# adapter.net
KiCad netlist of a schematic drawn in EAGLE
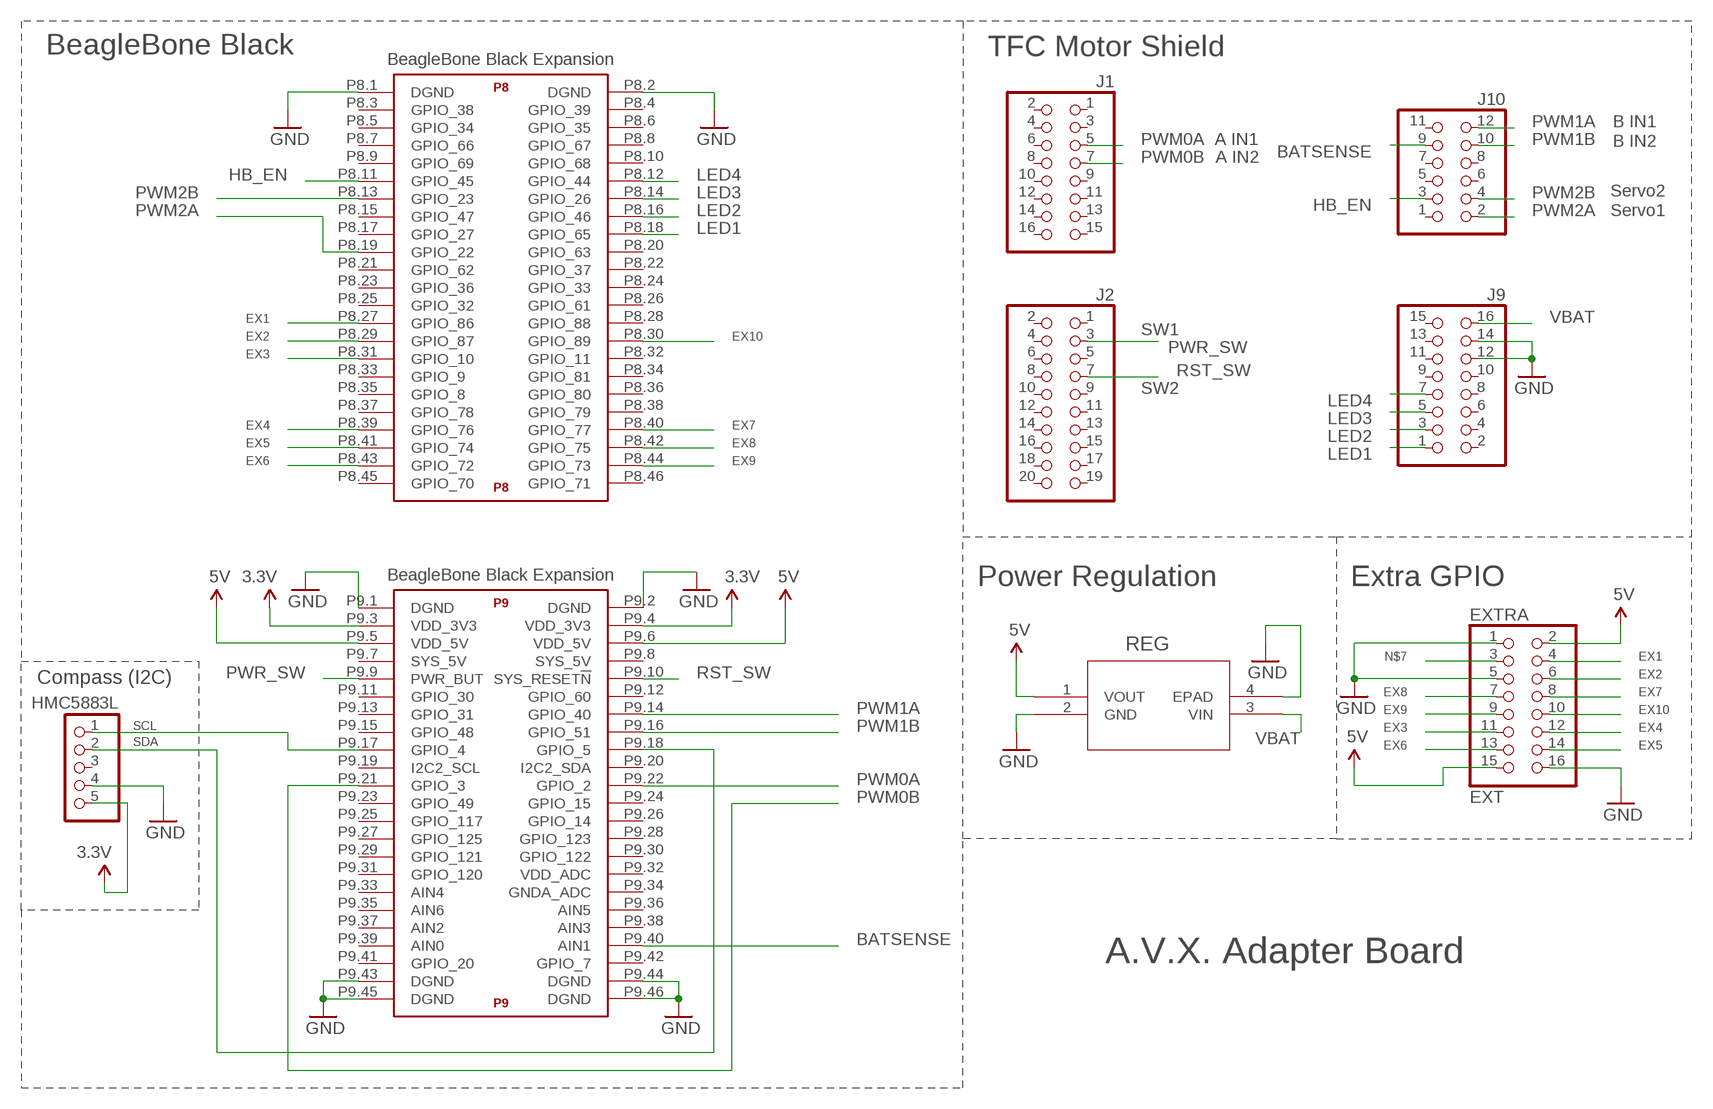
[diagram p0: schematic, sheet 1]

(export (version "E")
  (design (tool "Eeschema 10.0.6"))
  (components
    (comp (ref "COMPASS")
      (value "HMC5883L")
      (footprint "eagle-import:1X05")
      (libsource (lib "eagle-import") (part "PINHD-1X5"))
    )
    (comp (ref "EXTRA")
      (value "EXT")
      (footprint "eagle-import:2X08")
      (libsource (lib "eagle-import") (part "PINHD-2X8"))
    )
    (comp (ref "J1")
      (value "PINHD-2X8")
      (footprint "eagle-import:2X08")
      (libsource (lib "eagle-import") (part "PINHD-2X8"))
    )
    (comp (ref "J2")
      (value "PINHD-2X10")
      (footprint "eagle-import:2X10")
      (libsource (lib "eagle-import") (part "PINHD-2X10"))
    )
    (comp (ref "J9")
      (value "PINHD-2X8")
      (footprint "eagle-import:2X08")
      (libsource (lib "eagle-import") (part "PINHD-2X8"))
    )
    (comp (ref "J10")
      (value "PINHD-2X6")
      (footprint "eagle-import:2X06")
      (libsource (lib "eagle-import") (part "PINHD-2X6"))
    )
    (comp (ref "REG")
      (value "UCC383-5_KTT_3")
      (footprint "eagle-import:KTT3_6P22X6P6")
      (fields
        (field (name "GENERIC_PART_NUMBER") "UCC383-5")
        (field (name "MANUFACTURER") "Texas Instruments")
        (field (name "MANUFACTURER_PART_NUMBER") "ucc383-5_ktt_3")
      )
      (libsource (lib "eagle-import") (part "UCC383-5_KTT_3"))
    )
    (comp (ref "U$1")
      (value "BEAGLE_BONE_BLACK_CAPE")
      (footprint "eagle-import:BEAGLE_BONE_BLACK_CAPE")
      (libsource (lib "eagle-import") (part "BEAGLE_BONE_BLACK_CAPE"))
    )
  )
  (nets
    (net (code "1") (name "/BATSENSE") (class "Default")
      (node (ref "J10") (pin "9") (pinfunction "9_9") (pintype "passive"))
      (node (ref "U$1") (pin "P9.40") (pinfunction "AIN1_P9.40") (pintype "bidirectional"))
    )
    (net (code "2") (name "/EX1") (class "Default")
      (node (ref "EXTRA") (pin "4") (pinfunction "4_4") (pintype "passive"))
      (node (ref "U$1") (pin "P8.27") (pinfunction "GPIO_86_P8.27") (pintype "bidirectional"))
    )
    (net (code "3") (name "/EX2") (class "Default")
      (node (ref "EXTRA") (pin "6") (pinfunction "6_6") (pintype "passive"))
      (node (ref "U$1") (pin "P8.29") (pinfunction "GPIO_87_P8.29") (pintype "bidirectional"))
    )
    (net (code "4") (name "/EX3") (class "Default")
      (node (ref "EXTRA") (pin "11") (pinfunction "11_11") (pintype "passive"))
      (node (ref "U$1") (pin "P8.31") (pinfunction "GPIO_10_P8.31") (pintype "bidirectional"))
    )
    (net (code "5") (name "/EX4") (class "Default")
      (node (ref "EXTRA") (pin "12") (pinfunction "12_12") (pintype "passive"))
      (node (ref "U$1") (pin "P8.39") (pinfunction "GPIO_76_P8.39") (pintype "bidirectional"))
    )
    (net (code "6") (name "/EX5") (class "Default")
      (node (ref "EXTRA") (pin "14") (pinfunction "14_14") (pintype "passive"))
      (node (ref "U$1") (pin "P8.41") (pinfunction "GPIO_74_P8.41") (pintype "bidirectional"))
    )
    (net (code "7") (name "/EX6") (class "Default")
      (node (ref "EXTRA") (pin "13") (pinfunction "13_13") (pintype "passive"))
      (node (ref "U$1") (pin "P8.43") (pinfunction "GPIO_72_P8.43") (pintype "bidirectional"))
    )
    (net (code "8") (name "/EX7") (class "Default")
      (node (ref "EXTRA") (pin "8") (pinfunction "8_8") (pintype "passive"))
      (node (ref "U$1") (pin "P8.40") (pinfunction "GPIO_77_P8.40") (pintype "bidirectional"))
    )
    (net (code "9") (name "/EX8") (class "Default")
      (node (ref "EXTRA") (pin "7") (pinfunction "7_7") (pintype "passive"))
      (node (ref "U$1") (pin "P8.42") (pinfunction "GPIO_75_P8.42") (pintype "bidirectional"))
    )
    (net (code "10") (name "/EX9") (class "Default")
      (node (ref "EXTRA") (pin "9") (pinfunction "9_9") (pintype "passive"))
      (node (ref "U$1") (pin "P8.44") (pinfunction "GPIO_73_P8.44") (pintype "bidirectional"))
    )
    (net (code "11") (name "/EX10") (class "Default")
      (node (ref "EXTRA") (pin "10") (pinfunction "10_10") (pintype "passive"))
      (node (ref "U$1") (pin "P8.30") (pinfunction "GPIO_89_P8.30") (pintype "bidirectional"))
    )
    (net (code "12") (name "/HB_EN") (class "Default")
      (node (ref "J10") (pin "3") (pinfunction "3_3") (pintype "passive"))
      (node (ref "U$1") (pin "P8.11") (pinfunction "GPIO_45_P8.11") (pintype "bidirectional"))
    )
    (net (code "13") (name "/LED1") (class "Default")
      (node (ref "J9") (pin "1") (pinfunction "1_1") (pintype "passive"))
      (node (ref "U$1") (pin "P8.18") (pinfunction "GPIO_65_P8.18") (pintype "bidirectional"))
    )
    (net (code "14") (name "/LED2") (class "Default")
      (node (ref "J9") (pin "3") (pinfunction "3_3") (pintype "passive"))
      (node (ref "U$1") (pin "P8.16") (pinfunction "GPIO_46_P8.16") (pintype "bidirectional"))
    )
    (net (code "15") (name "/LED3") (class "Default")
      (node (ref "J9") (pin "5") (pinfunction "5_5") (pintype "passive"))
      (node (ref "U$1") (pin "P8.14") (pinfunction "GPIO_26_P8.14") (pintype "bidirectional"))
    )
    (net (code "16") (name "/LED4") (class "Default")
      (node (ref "J9") (pin "7") (pinfunction "7_7") (pintype "passive"))
      (node (ref "U$1") (pin "P8.12") (pinfunction "GPIO_44_P8.12") (pintype "bidirectional"))
    )
    (net (code "17") (name "/N$7") (class "Default")
      (node (ref "EXTRA") (pin "3") (pinfunction "3_3") (pintype "passive"))
    )
    (net (code "18") (name "/PWM0A") (class "Default")
      (node (ref "J1") (pin "5") (pinfunction "5_5") (pintype "passive"))
      (node (ref "U$1") (pin "P9.22") (pinfunction "GPIO_2_P9.22") (pintype "bidirectional"))
    )
    (net (code "19") (name "/PWM0B") (class "Default")
      (node (ref "J1") (pin "7") (pinfunction "7_7") (pintype "passive"))
      (node (ref "U$1") (pin "P9.21") (pinfunction "GPIO_3_P9.21") (pintype "bidirectional"))
    )
    (net (code "20") (name "/PWM1A") (class "Default")
      (node (ref "J10") (pin "12") (pinfunction "12_12") (pintype "passive"))
      (node (ref "U$1") (pin "P9.14") (pinfunction "GPIO_40_P9.14") (pintype "bidirectional"))
    )
    (net (code "21") (name "/PWM1B") (class "Default")
      (node (ref "J10") (pin "10") (pinfunction "10_10") (pintype "passive"))
      (node (ref "U$1") (pin "P9.16") (pinfunction "GPIO_51_P9.16") (pintype "bidirectional"))
    )
    (net (code "22") (name "/PWM2A") (class "Default")
      (node (ref "J10") (pin "2") (pinfunction "2_2") (pintype "passive"))
      (node (ref "U$1") (pin "P8.19") (pinfunction "GPIO_22_P8.19") (pintype "bidirectional"))
    )
    (net (code "23") (name "/PWM2B") (class "Default")
      (node (ref "J10") (pin "4") (pinfunction "4_4") (pintype "passive"))
      (node (ref "U$1") (pin "P8.13") (pinfunction "GPIO_23_P8.13") (pintype "bidirectional"))
    )
    (net (code "24") (name "/PWR_SW") (class "Default")
      (node (ref "J2") (pin "3") (pinfunction "3_3") (pintype "passive"))
      (node (ref "U$1") (pin "P9.9") (pinfunction "PWR_BUT_P9.9") (pintype "bidirectional"))
    )
    (net (code "25") (name "/RST_SW") (class "Default")
      (node (ref "J2") (pin "7") (pinfunction "7_7") (pintype "passive"))
      (node (ref "U$1") (pin "P9.10") (pinfunction "SYS_RESET~{N}_P9.10") (pintype "bidirectional"))
    )
    (net (code "26") (name "/VBAT") (class "Default")
      (node (ref "J9") (pin "16") (pinfunction "16_16") (pintype "passive"))
      (node (ref "REG") (pin "3") (pinfunction "VIN_3") (pintype "input"))
    )
    (net (code "27") (name "3.3V") (class "Default")
      (node (ref "COMPASS") (pin "5") (pinfunction "5_5") (pintype "passive"))
      (node (ref "U$1") (pin "P9.3") (pinfunction "VDD_3V3_P9.3") (pintype "bidirectional"))
      (node (ref "U$1") (pin "P9.4") (pinfunction "VDD_3V3_P9.4") (pintype "bidirectional"))
    )
    (net (code "28") (name "5V") (class "Default")
      (node (ref "EXTRA") (pin "15") (pinfunction "15_15") (pintype "passive"))
      (node (ref "EXTRA") (pin "2") (pinfunction "2_2") (pintype "passive"))
      (node (ref "REG") (pin "1") (pinfunction "VOUT_1") (pintype "output"))
      (node (ref "U$1") (pin "P9.5") (pinfunction "VDD_5V_P9.5") (pintype "bidirectional"))
      (node (ref "U$1") (pin "P9.6") (pinfunction "VDD_5V_P9.6") (pintype "bidirectional"))
    )
    (net (code "29") (name "GND") (class "Default")
      (node (ref "COMPASS") (pin "4") (pinfunction "4_4") (pintype "passive"))
      (node (ref "EXTRA") (pin "1") (pinfunction "1_1") (pintype "passive"))
      (node (ref "EXTRA") (pin "16") (pinfunction "16_16") (pintype "passive"))
      (node (ref "EXTRA") (pin "5") (pinfunction "5_5") (pintype "passive"))
      (node (ref "J9") (pin "12") (pinfunction "12_12") (pintype "passive"))
      (node (ref "J9") (pin "14") (pinfunction "14_14") (pintype "passive"))
      (node (ref "REG") (pin "2") (pinfunction "GND_2") (pintype "power_in"))
      (node (ref "REG") (pin "4") (pinfunction "EPAD_4") (pintype "passive"))
      (node (ref "U$1") (pin "P8.1") (pinfunction "DGND_P8.1") (pintype "bidirectional"))
      (node (ref "U$1") (pin "P8.2") (pinfunction "DGND_P8.2") (pintype "bidirectional"))
      (node (ref "U$1") (pin "P9.1") (pinfunction "DGND_P9.1") (pintype "bidirectional"))
      (node (ref "U$1") (pin "P9.2") (pinfunction "DGND_P9.2") (pintype "bidirectional"))
      (node (ref "U$1") (pin "P9.43") (pinfunction "DGND_P9.43") (pintype "bidirectional"))
      (node (ref "U$1") (pin "P9.44") (pinfunction "DGND_P9.44") (pintype "bidirectional"))
      (node (ref "U$1") (pin "P9.45") (pinfunction "DGND_P9.45") (pintype "bidirectional"))
      (node (ref "U$1") (pin "P9.46") (pinfunction "DGND_P9.46") (pintype "bidirectional"))
    )
    (net (code "30") (name "Net-(U$1B-GPIO_4)") (class "Default")
      (node (ref "COMPASS") (pin "1") (pinfunction "1_1") (pintype "passive"))
      (node (ref "U$1") (pin "P9.17") (pinfunction "GPIO_4_P9.17") (pintype "bidirectional"))
    )
    (net (code "31") (name "Net-(U$1B-GPIO_5)") (class "Default")
      (node (ref "COMPASS") (pin "2") (pinfunction "2_2") (pintype "passive"))
      (node (ref "U$1") (pin "P9.18") (pinfunction "GPIO_5_P9.18") (pintype "bidirectional"))
    )
    (net (code "32") (name "unconnected-(COMPASS-Pad3)") (class "Default")
      (node (ref "COMPASS") (pin "3") (pinfunction "3_3") (pintype "passive"))
    )
    (net (code "33") (name "unconnected-(J1-Pad1)") (class "Default")
      (node (ref "J1") (pin "1") (pinfunction "1_1") (pintype "passive"))
    )
    (net (code "34") (name "unconnected-(J1-Pad2)") (class "Default")
      (node (ref "J1") (pin "2") (pinfunction "2_2") (pintype "passive"))
    )
    (net (code "35") (name "unconnected-(J1-Pad3)") (class "Default")
      (node (ref "J1") (pin "3") (pinfunction "3_3") (pintype "passive"))
    )
    (net (code "36") (name "unconnected-(J1-Pad4)") (class "Default")
      (node (ref "J1") (pin "4") (pinfunction "4_4") (pintype "passive"))
    )
    (net (code "37") (name "unconnected-(J1-Pad6)") (class "Default")
      (node (ref "J1") (pin "6") (pinfunction "6_6") (pintype "passive"))
    )
    (net (code "38") (name "unconnected-(J1-Pad8)") (class "Default")
      (node (ref "J1") (pin "8") (pinfunction "8_8") (pintype "passive"))
    )
    (net (code "39") (name "unconnected-(J1-Pad9)") (class "Default")
      (node (ref "J1") (pin "9") (pinfunction "9_9") (pintype "passive"))
    )
    (net (code "40") (name "unconnected-(J1-Pad10)") (class "Default")
      (node (ref "J1") (pin "10") (pinfunction "10_10") (pintype "passive"))
    )
    (net (code "41") (name "unconnected-(J1-Pad11)") (class "Default")
      (node (ref "J1") (pin "11") (pinfunction "11_11") (pintype "passive"))
    )
    (net (code "42") (name "unconnected-(J1-Pad12)") (class "Default")
      (node (ref "J1") (pin "12") (pinfunction "12_12") (pintype "passive"))
    )
    (net (code "43") (name "unconnected-(J1-Pad13)") (class "Default")
      (node (ref "J1") (pin "13") (pinfunction "13_13") (pintype "passive"))
    )
    (net (code "44") (name "unconnected-(J1-Pad14)") (class "Default")
      (node (ref "J1") (pin "14") (pinfunction "14_14") (pintype "passive"))
    )
    (net (code "45") (name "unconnected-(J1-Pad15)") (class "Default")
      (node (ref "J1") (pin "15") (pinfunction "15_15") (pintype "passive"))
    )
    (net (code "46") (name "unconnected-(J1-Pad16)") (class "Default")
      (node (ref "J1") (pin "16") (pinfunction "16_16") (pintype "passive"))
    )
    (net (code "47") (name "unconnected-(J2-Pad1)") (class "Default")
      (node (ref "J2") (pin "1") (pinfunction "1_1") (pintype "passive"))
    )
    (net (code "48") (name "unconnected-(J2-Pad2)") (class "Default")
      (node (ref "J2") (pin "2") (pinfunction "2_2") (pintype "passive"))
    )
    (net (code "49") (name "unconnected-(J2-Pad4)") (class "Default")
      (node (ref "J2") (pin "4") (pinfunction "4_4") (pintype "passive"))
    )
    (net (code "50") (name "unconnected-(J2-Pad5)") (class "Default")
      (node (ref "J2") (pin "5") (pinfunction "5_5") (pintype "passive"))
    )
    (net (code "51") (name "unconnected-(J2-Pad6)") (class "Default")
      (node (ref "J2") (pin "6") (pinfunction "6_6") (pintype "passive"))
    )
    (net (code "52") (name "unconnected-(J2-Pad8)") (class "Default")
      (node (ref "J2") (pin "8") (pinfunction "8_8") (pintype "passive"))
    )
    (net (code "53") (name "unconnected-(J2-Pad9)") (class "Default")
      (node (ref "J2") (pin "9") (pinfunction "9_9") (pintype "passive"))
    )
    (net (code "54") (name "unconnected-(J2-Pad10)") (class "Default")
      (node (ref "J2") (pin "10") (pinfunction "10_10") (pintype "passive"))
    )
    (net (code "55") (name "unconnected-(J2-Pad11)") (class "Default")
      (node (ref "J2") (pin "11") (pinfunction "11_11") (pintype "passive"))
    )
    (net (code "56") (name "unconnected-(J2-Pad12)") (class "Default")
      (node (ref "J2") (pin "12") (pinfunction "12_12") (pintype "passive"))
    )
    (net (code "57") (name "unconnected-(J2-Pad13)") (class "Default")
      (node (ref "J2") (pin "13") (pinfunction "13_13") (pintype "passive"))
    )
    (net (code "58") (name "unconnected-(J2-Pad14)") (class "Default")
      (node (ref "J2") (pin "14") (pinfunction "14_14") (pintype "passive"))
    )
    (net (code "59") (name "unconnected-(J2-Pad15)") (class "Default")
      (node (ref "J2") (pin "15") (pinfunction "15_15") (pintype "passive"))
    )
    (net (code "60") (name "unconnected-(J2-Pad16)") (class "Default")
      (node (ref "J2") (pin "16") (pinfunction "16_16") (pintype "passive"))
    )
    (net (code "61") (name "unconnected-(J2-Pad17)") (class "Default")
      (node (ref "J2") (pin "17") (pinfunction "17_17") (pintype "passive"))
    )
    (net (code "62") (name "unconnected-(J2-Pad18)") (class "Default")
      (node (ref "J2") (pin "18") (pinfunction "18_18") (pintype "passive"))
    )
    (net (code "63") (name "unconnected-(J2-Pad19)") (class "Default")
      (node (ref "J2") (pin "19") (pinfunction "19_19") (pintype "passive"))
    )
    (net (code "64") (name "unconnected-(J2-Pad20)") (class "Default")
      (node (ref "J2") (pin "20") (pinfunction "20_20") (pintype "passive"))
    )
    (net (code "65") (name "unconnected-(J9-Pad2)") (class "Default")
      (node (ref "J9") (pin "2") (pinfunction "2_2") (pintype "passive"))
    )
    (net (code "66") (name "unconnected-(J9-Pad4)") (class "Default")
      (node (ref "J9") (pin "4") (pinfunction "4_4") (pintype "passive"))
    )
    (net (code "67") (name "unconnected-(J9-Pad6)") (class "Default")
      (node (ref "J9") (pin "6") (pinfunction "6_6") (pintype "passive"))
    )
    (net (code "68") (name "unconnected-(J9-Pad8)") (class "Default")
      (node (ref "J9") (pin "8") (pinfunction "8_8") (pintype "passive"))
    )
    (net (code "69") (name "unconnected-(J9-Pad9)") (class "Default")
      (node (ref "J9") (pin "9") (pinfunction "9_9") (pintype "passive"))
    )
    (net (code "70") (name "unconnected-(J9-Pad10)") (class "Default")
      (node (ref "J9") (pin "10") (pinfunction "10_10") (pintype "passive"))
    )
    (net (code "71") (name "unconnected-(J9-Pad11)") (class "Default")
      (node (ref "J9") (pin "11") (pinfunction "11_11") (pintype "passive"))
    )
    (net (code "72") (name "unconnected-(J9-Pad13)") (class "Default")
      (node (ref "J9") (pin "13") (pinfunction "13_13") (pintype "passive"))
    )
    (net (code "73") (name "unconnected-(J9-Pad15)") (class "Default")
      (node (ref "J9") (pin "15") (pinfunction "15_15") (pintype "passive"))
    )
    (net (code "74") (name "unconnected-(J10-Pad1)") (class "Default")
      (node (ref "J10") (pin "1") (pinfunction "1_1") (pintype "passive"))
    )
    (net (code "75") (name "unconnected-(J10-Pad5)") (class "Default")
      (node (ref "J10") (pin "5") (pinfunction "5_5") (pintype "passive"))
    )
    (net (code "76") (name "unconnected-(J10-Pad6)") (class "Default")
      (node (ref "J10") (pin "6") (pinfunction "6_6") (pintype "passive"))
    )
    (net (code "77") (name "unconnected-(J10-Pad7)") (class "Default")
      (node (ref "J10") (pin "7") (pinfunction "7_7") (pintype "passive"))
    )
    (net (code "78") (name "unconnected-(J10-Pad8)") (class "Default")
      (node (ref "J10") (pin "8") (pinfunction "8_8") (pintype "passive"))
    )
    (net (code "79") (name "unconnected-(J10-Pad11)") (class "Default")
      (node (ref "J10") (pin "11") (pinfunction "11_11") (pintype "passive"))
    )
    (net (code "80") (name "unconnected-(U$1A-GPIO_8-PadP8.35)") (class "Default")
      (node (ref "U$1") (pin "P8.35") (pinfunction "GPIO_8_P8.35") (pintype "bidirectional"))
    )
    (net (code "81") (name "unconnected-(U$1A-GPIO_9-PadP8.33)") (class "Default")
      (node (ref "U$1") (pin "P8.33") (pinfunction "GPIO_9_P8.33") (pintype "bidirectional"))
    )
    (net (code "82") (name "unconnected-(U$1A-GPIO_11-PadP8.32)") (class "Default")
      (node (ref "U$1") (pin "P8.32") (pinfunction "GPIO_11_P8.32") (pintype "bidirectional"))
    )
    (net (code "83") (name "unconnected-(U$1A-GPIO_27-PadP8.17)") (class "Default")
      (node (ref "U$1") (pin "P8.17") (pinfunction "GPIO_27_P8.17") (pintype "bidirectional"))
    )
    (net (code "84") (name "unconnected-(U$1A-GPIO_32-PadP8.25)") (class "Default")
      (node (ref "U$1") (pin "P8.25") (pinfunction "GPIO_32_P8.25") (pintype "bidirectional"))
    )
    (net (code "85") (name "unconnected-(U$1A-GPIO_33-PadP8.24)") (class "Default")
      (node (ref "U$1") (pin "P8.24") (pinfunction "GPIO_33_P8.24") (pintype "bidirectional"))
    )
    (net (code "86") (name "unconnected-(U$1A-GPIO_34-PadP8.5)") (class "Default")
      (node (ref "U$1") (pin "P8.5") (pinfunction "GPIO_34_P8.5") (pintype "bidirectional"))
    )
    (net (code "87") (name "unconnected-(U$1A-GPIO_35-PadP8.6)") (class "Default")
      (node (ref "U$1") (pin "P8.6") (pinfunction "GPIO_35_P8.6") (pintype "bidirectional"))
    )
    (net (code "88") (name "unconnected-(U$1A-GPIO_36-PadP8.23)") (class "Default")
      (node (ref "U$1") (pin "P8.23") (pinfunction "GPIO_36_P8.23") (pintype "bidirectional"))
    )
    (net (code "89") (name "unconnected-(U$1A-GPIO_37-PadP8.22)") (class "Default")
      (node (ref "U$1") (pin "P8.22") (pinfunction "GPIO_37_P8.22") (pintype "bidirectional"))
    )
    (net (code "90") (name "unconnected-(U$1A-GPIO_38-PadP8.3)") (class "Default")
      (node (ref "U$1") (pin "P8.3") (pinfunction "GPIO_38_P8.3") (pintype "bidirectional"))
    )
    (net (code "91") (name "unconnected-(U$1A-GPIO_39-PadP8.4)") (class "Default")
      (node (ref "U$1") (pin "P8.4") (pinfunction "GPIO_39_P8.4") (pintype "bidirectional"))
    )
    (net (code "92") (name "unconnected-(U$1A-GPIO_47-PadP8.15)") (class "Default")
      (node (ref "U$1") (pin "P8.15") (pinfunction "GPIO_47_P8.15") (pintype "bidirectional"))
    )
    (net (code "93") (name "unconnected-(U$1A-GPIO_61-PadP8.26)") (class "Default")
      (node (ref "U$1") (pin "P8.26") (pinfunction "GPIO_61_P8.26") (pintype "bidirectional"))
    )
    (net (code "94") (name "unconnected-(U$1A-GPIO_62-PadP8.21)") (class "Default")
      (node (ref "U$1") (pin "P8.21") (pinfunction "GPIO_62_P8.21") (pintype "bidirectional"))
    )
    (net (code "95") (name "unconnected-(U$1A-GPIO_63-PadP8.20)") (class "Default")
      (node (ref "U$1") (pin "P8.20") (pinfunction "GPIO_63_P8.20") (pintype "bidirectional"))
    )
    (net (code "96") (name "unconnected-(U$1A-GPIO_66-PadP8.7)") (class "Default")
      (node (ref "U$1") (pin "P8.7") (pinfunction "GPIO_66_P8.7") (pintype "bidirectional"))
    )
    (net (code "97") (name "unconnected-(U$1A-GPIO_67-PadP8.8)") (class "Default")
      (node (ref "U$1") (pin "P8.8") (pinfunction "GPIO_67_P8.8") (pintype "bidirectional"))
    )
    (net (code "98") (name "unconnected-(U$1A-GPIO_68-PadP8.10)") (class "Default")
      (node (ref "U$1") (pin "P8.10") (pinfunction "GPIO_68_P8.10") (pintype "bidirectional"))
    )
    (net (code "99") (name "unconnected-(U$1A-GPIO_69-PadP8.9)") (class "Default")
      (node (ref "U$1") (pin "P8.9") (pinfunction "GPIO_69_P8.9") (pintype "bidirectional"))
    )
    (net (code "100") (name "unconnected-(U$1A-GPIO_70-PadP8.45)") (class "Default")
      (node (ref "U$1") (pin "P8.45") (pinfunction "GPIO_70_P8.45") (pintype "bidirectional"))
    )
    (net (code "101") (name "unconnected-(U$1A-GPIO_71-PadP8.46)") (class "Default")
      (node (ref "U$1") (pin "P8.46") (pinfunction "GPIO_71_P8.46") (pintype "bidirectional"))
    )
    (net (code "102") (name "unconnected-(U$1A-GPIO_78-PadP8.37)") (class "Default")
      (node (ref "U$1") (pin "P8.37") (pinfunction "GPIO_78_P8.37") (pintype "bidirectional"))
    )
    (net (code "103") (name "unconnected-(U$1A-GPIO_79-PadP8.38)") (class "Default")
      (node (ref "U$1") (pin "P8.38") (pinfunction "GPIO_79_P8.38") (pintype "bidirectional"))
    )
    (net (code "104") (name "unconnected-(U$1A-GPIO_80-PadP8.36)") (class "Default")
      (node (ref "U$1") (pin "P8.36") (pinfunction "GPIO_80_P8.36") (pintype "bidirectional"))
    )
    (net (code "105") (name "unconnected-(U$1A-GPIO_81-PadP8.34)") (class "Default")
      (node (ref "U$1") (pin "P8.34") (pinfunction "GPIO_81_P8.34") (pintype "bidirectional"))
    )
    (net (code "106") (name "unconnected-(U$1A-GPIO_88-PadP8.28)") (class "Default")
      (node (ref "U$1") (pin "P8.28") (pinfunction "GPIO_88_P8.28") (pintype "bidirectional"))
    )
    (net (code "107") (name "unconnected-(U$1B-AIN0-PadP9.39)") (class "Default")
      (node (ref "U$1") (pin "P9.39") (pinfunction "AIN0_P9.39") (pintype "bidirectional"))
    )
    (net (code "108") (name "unconnected-(U$1B-AIN2-PadP9.37)") (class "Default")
      (node (ref "U$1") (pin "P9.37") (pinfunction "AIN2_P9.37") (pintype "bidirectional"))
    )
    (net (code "109") (name "unconnected-(U$1B-AIN3-PadP9.38)") (class "Default")
      (node (ref "U$1") (pin "P9.38") (pinfunction "AIN3_P9.38") (pintype "bidirectional"))
    )
    (net (code "110") (name "unconnected-(U$1B-AIN4-PadP9.33)") (class "Default")
      (node (ref "U$1") (pin "P9.33") (pinfunction "AIN4_P9.33") (pintype "bidirectional"))
    )
    (net (code "111") (name "unconnected-(U$1B-AIN5-PadP9.36)") (class "Default")
      (node (ref "U$1") (pin "P9.36") (pinfunction "AIN5_P9.36") (pintype "bidirectional"))
    )
    (net (code "112") (name "unconnected-(U$1B-AIN6-PadP9.35)") (class "Default")
      (node (ref "U$1") (pin "P9.35") (pinfunction "AIN6_P9.35") (pintype "bidirectional"))
    )
    (net (code "113") (name "unconnected-(U$1B-GNDA_ADC-PadP9.34)") (class "Default")
      (node (ref "U$1") (pin "P9.34") (pinfunction "GNDA_ADC_P9.34") (pintype "bidirectional"))
    )
    (net (code "114") (name "unconnected-(U$1B-GPIO_7-PadP9.42)") (class "Default")
      (node (ref "U$1") (pin "P9.42") (pinfunction "GPIO_7_P9.42") (pintype "bidirectional"))
    )
    (net (code "115") (name "unconnected-(U$1B-GPIO_14-PadP9.26)") (class "Default")
      (node (ref "U$1") (pin "P9.26") (pinfunction "GPIO_14_P9.26") (pintype "bidirectional"))
    )
    (net (code "116") (name "unconnected-(U$1B-GPIO_15-PadP9.24)") (class "Default")
      (node (ref "U$1") (pin "P9.24") (pinfunction "GPIO_15_P9.24") (pintype "bidirectional"))
    )
    (net (code "117") (name "unconnected-(U$1B-GPIO_20-PadP9.41)") (class "Default")
      (node (ref "U$1") (pin "P9.41") (pinfunction "GPIO_20_P9.41") (pintype "bidirectional"))
    )
    (net (code "118") (name "unconnected-(U$1B-GPIO_30-PadP9.11)") (class "Default")
      (node (ref "U$1") (pin "P9.11") (pinfunction "GPIO_30_P9.11") (pintype "bidirectional"))
    )
    (net (code "119") (name "unconnected-(U$1B-GPIO_31-PadP9.13)") (class "Default")
      (node (ref "U$1") (pin "P9.13") (pinfunction "GPIO_31_P9.13") (pintype "bidirectional"))
    )
    (net (code "120") (name "unconnected-(U$1B-GPIO_48-PadP9.15)") (class "Default")
      (node (ref "U$1") (pin "P9.15") (pinfunction "GPIO_48_P9.15") (pintype "bidirectional"))
    )
    (net (code "121") (name "unconnected-(U$1B-GPIO_49-PadP9.23)") (class "Default")
      (node (ref "U$1") (pin "P9.23") (pinfunction "GPIO_49_P9.23") (pintype "bidirectional"))
    )
    (net (code "122") (name "unconnected-(U$1B-GPIO_60-PadP9.12)") (class "Default")
      (node (ref "U$1") (pin "P9.12") (pinfunction "GPIO_60_P9.12") (pintype "bidirectional"))
    )
    (net (code "123") (name "unconnected-(U$1B-GPIO_117-PadP9.25)") (class "Default")
      (node (ref "U$1") (pin "P9.25") (pinfunction "GPIO_117_P9.25") (pintype "bidirectional"))
    )
    (net (code "124") (name "unconnected-(U$1B-GPIO_120-PadP9.31)") (class "Default")
      (node (ref "U$1") (pin "P9.31") (pinfunction "GPIO_120_P9.31") (pintype "bidirectional"))
    )
    (net (code "125") (name "unconnected-(U$1B-GPIO_121-PadP9.29)") (class "Default")
      (node (ref "U$1") (pin "P9.29") (pinfunction "GPIO_121_P9.29") (pintype "bidirectional"))
    )
    (net (code "126") (name "unconnected-(U$1B-GPIO_122-PadP9.30)") (class "Default")
      (node (ref "U$1") (pin "P9.30") (pinfunction "GPIO_122_P9.30") (pintype "bidirectional"))
    )
    (net (code "127") (name "unconnected-(U$1B-GPIO_123-PadP9.28)") (class "Default")
      (node (ref "U$1") (pin "P9.28") (pinfunction "GPIO_123_P9.28") (pintype "bidirectional"))
    )
    (net (code "128") (name "unconnected-(U$1B-GPIO_125-PadP9.27)") (class "Default")
      (node (ref "U$1") (pin "P9.27") (pinfunction "GPIO_125_P9.27") (pintype "bidirectional"))
    )
    (net (code "129") (name "unconnected-(U$1B-I2C2_SCL-PadP9.19)") (class "Default")
      (node (ref "U$1") (pin "P9.19") (pinfunction "I2C2_SCL_P9.19") (pintype "bidirectional"))
    )
    (net (code "130") (name "unconnected-(U$1B-I2C2_SDA-PadP9.20)") (class "Default")
      (node (ref "U$1") (pin "P9.20") (pinfunction "I2C2_SDA_P9.20") (pintype "bidirectional"))
    )
    (net (code "131") (name "unconnected-(U$1B-SYS_5V-PadP9.7)") (class "Default")
      (node (ref "U$1") (pin "P9.7") (pinfunction "SYS_5V_P9.7") (pintype "bidirectional"))
    )
    (net (code "132") (name "unconnected-(U$1B-SYS_5V-PadP9.8)") (class "Default")
      (node (ref "U$1") (pin "P9.8") (pinfunction "SYS_5V_P9.8") (pintype "bidirectional"))
    )
    (net (code "133") (name "unconnected-(U$1B-VDD_ADC-PadP9.32)") (class "Default")
      (node (ref "U$1") (pin "P9.32") (pinfunction "VDD_ADC_P9.32") (pintype "bidirectional"))
    )
  )
)
